# 05_COMMUNICATION.net
KiCad netlist of a schematic drawn in Altium Designer
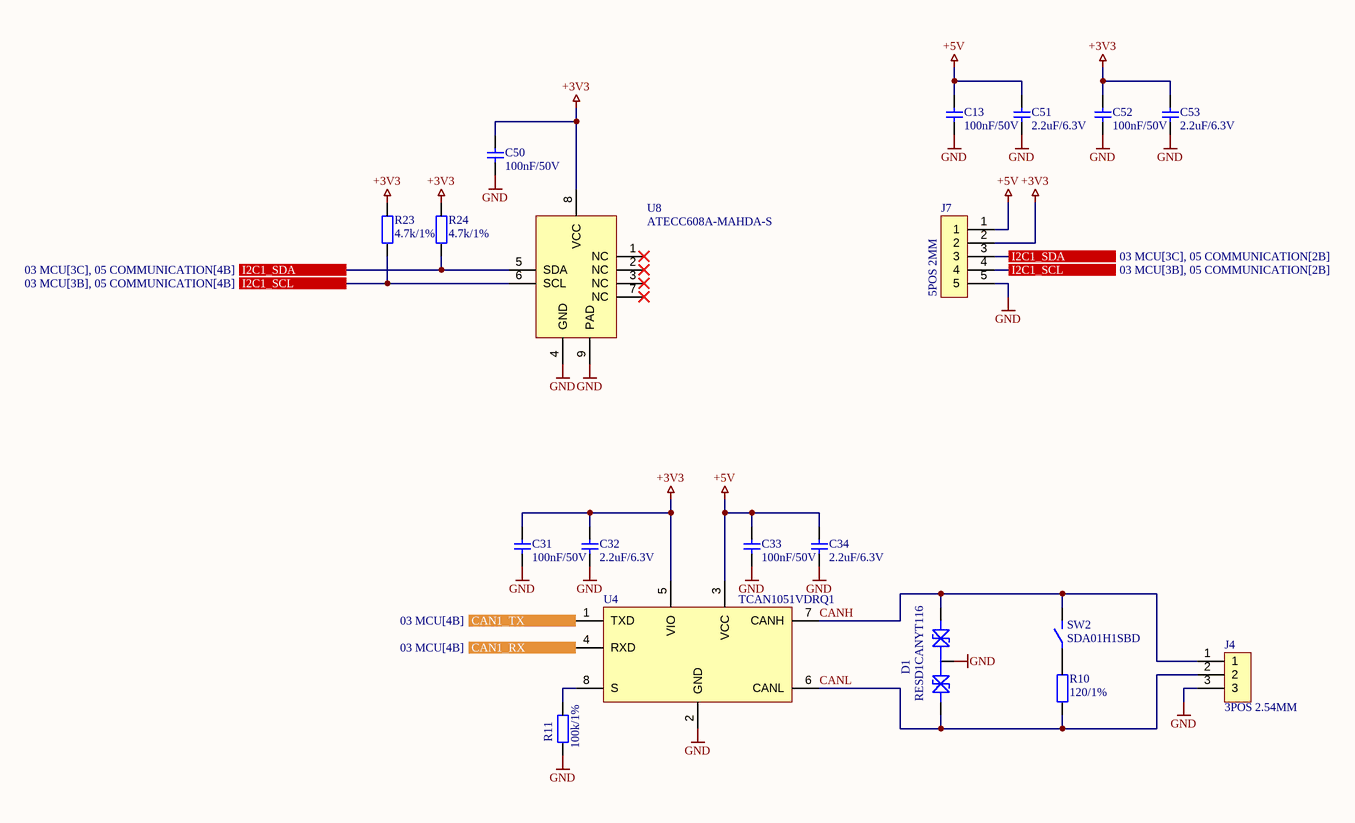
[diagram p0: 05 COMMUNICATION.SchDoc]

(export (version "E")
  (design (tool "Eeschema 10.0.6"))
  (components
    (comp (ref "C13")
      (value "100nF/50V")
      (footprint "CAPC1005X06M-0402")
      (description "0.1 µF ±10% 50V Ceramic Capacitor X7R 0402 (1005 Metric)")
      (fields (field (name "MPN") "GRM155R71H104KE14D"))
      (libsource (lib "Symbol") (part "GRM155R71H104KE14D"))
    )
    (comp (ref "C31")
      (value "100nF/50V")
      (footprint "CAPC1005X06M-0402")
      (description "0.1 µF ±10% 50V Ceramic Capacitor X7R 0402 (1005 Metric)")
      (fields (field (name "MPN") "GRM155R71H104KE14D"))
      (libsource (lib "Symbol") (part "GRM155R71H104KE14D"))
    )
    (comp (ref "C32")
      (value "2.2uF/6.3V")
      (footprint "CAPC1005X06M-0402")
      (description "2.2 µF ±10% 6.3V Ceramic Capacitor X6S 0402 (1005 Metric)")
      (fields (field (name "MPN") "GRM155C80J225KE95D"))
      (libsource (lib "Symbol") (part "GRM155C80J225KE95D"))
    )
    (comp (ref "C33")
      (value "100nF/50V")
      (footprint "CAPC1005X06M-0402")
      (description "0.1 µF ±10% 50V Ceramic Capacitor X7R 0402 (1005 Metric)")
      (fields (field (name "MPN") "GRM155R71H104KE14D"))
      (libsource (lib "Symbol") (part "GRM155R71H104KE14D"))
    )
    (comp (ref "C34")
      (value "2.2uF/6.3V")
      (footprint "CAPC1005X06M-0402")
      (description "2.2 µF ±10% 6.3V Ceramic Capacitor X6S 0402 (1005 Metric)")
      (fields (field (name "MPN") "GRM155C80J225KE95D"))
      (libsource (lib "Symbol") (part "GRM155C80J225KE95D"))
    )
    (comp (ref "C50")
      (value "100nF/50V")
      (footprint "CAPC1005X06M-0402")
      (description "0.1 µF ±10% 50V Ceramic Capacitor X7R 0402 (1005 Metric)")
      (fields (field (name "MPN") "GRM155R71H104KE14D"))
      (libsource (lib "Symbol") (part "GRM155R71H104KE14D"))
    )
    (comp (ref "C51")
      (value "2.2uF/6.3V")
      (footprint "CAPC1005X06M-0402")
      (description "2.2 µF ±10% 6.3V Ceramic Capacitor X6S 0402 (1005 Metric)")
      (fields (field (name "MPN") "GRM155C80J225KE95D"))
      (libsource (lib "Symbol") (part "GRM155C80J225KE95D"))
    )
    (comp (ref "C52")
      (value "100nF/50V")
      (footprint "CAPC1005X06M-0402")
      (description "0.1 µF ±10% 50V Ceramic Capacitor X7R 0402 (1005 Metric)")
      (fields (field (name "MPN") "GRM155R71H104KE14D"))
      (libsource (lib "Symbol") (part "GRM155R71H104KE14D"))
    )
    (comp (ref "C53")
      (value "2.2uF/6.3V")
      (footprint "CAPC1005X06M-0402")
      (description "2.2 µF ±10% 6.3V Ceramic Capacitor X6S 0402 (1005 Metric)")
      (fields (field (name "MPN") "GRM155C80J225KE95D"))
      (libsource (lib "Symbol") (part "GRM155C80J225KE95D"))
    )
    (comp (ref "D1")
      (value "RESD1CANYT116")
      (footprint "SOT100P240X115-3N")
      (description "44V Clamp 8A (8/20µs) Ipp Tvs Diode Surface Mount SOT-23")
      (libsource (lib "Symbol") (part "RESD1CANYT116"))
    )
    (comp (ref "J4")
      (value "3POS 2.54MM")
      (footprint "282834-3")
      (description "3 Position Wire to Board Terminal Block Horizontal with Board 0.100\" (2.54mm) Through Hole")
      (fields (field (name "MPN") "282834-3"))
      (libsource (lib "Symbol") (part "282834-3"))
    )
    (comp (ref "J7")
      (value "5POS 2MM")
      (footprint "B5B-PH-K-S")
      (description "Connector Header Through Hole 5 position 0.079\" (2.00mm)")
      (fields (field (name "MPN") "B5B-PH-K-S"))
      (libsource (lib "Symbol") (part "B5B-PH-K-S"))
    )
    (comp (ref "R10")
      (value "120/1%")
      (footprint "RESC1005X04M-0402")
      (description "120 Ohms ±1% 0.063W, 1/16W Chip Resistor 0402 (1005 Metric) Moisture Resistant Thick Film")
      (fields (field (name "MPN") "RC0402FR-07120RL"))
      (libsource (lib "Symbol") (part "RC0402FR-07120RL"))
    )
    (comp (ref "R11")
      (value "100k/1%")
      (footprint "RESC1005X04M-0402")
      (description "100 kOhms ±1% 0.063W, 1/16W Chip Resistor 0402 (1005 Metric) Moisture Resistant Thick Film")
      (fields (field (name "MPN") "RC0402FR-07100KL"))
      (libsource (lib "Symbol") (part "RC0402FR-07100KL"))
    )
    (comp (ref "R23")
      (value "4.7k/1%")
      (footprint "RESC1005X04M-0402")
      (description "4.7 kOhms ±1% 0.063W, 1/16W Chip Resistor 0402 (1005 Metric) Moisture Resistant Thick Film")
      (fields (field (name "MPN") "RC0402FR-074K7L"))
      (libsource (lib "Symbol") (part "RC0402FR-074K7L"))
    )
    (comp (ref "R24")
      (value "4.7k/1%")
      (footprint "RESC1005X04M-0402")
      (description "4.7 kOhms ±1% 0.063W, 1/16W Chip Resistor 0402 (1005 Metric) Moisture Resistant Thick Film")
      (fields (field (name "MPN") "RC0402FR-074K7L"))
      (libsource (lib "Symbol") (part "RC0402FR-074K7L"))
    )
    (comp (ref "SW2")
      (value "SDA01H1SBD")
      (footprint "SDA01H1SB")
      (description "Dip Switch SPST 1 Position Surface Mount Slide (Standard) Actuator 25mA 24VDC")
      (libsource (lib "Symbol") (part "SDA01H1SBD"))
    )
    (comp (ref "U4")
      (value "TCAN1051VDRQ1")
      (footprint "SOIC127P600X175-8N")
      (description "1/1 Transceiver Half CANbus 8-SOIC")
      (libsource (lib "Symbol") (part "TCAN1051VDRQ1"))
    )
    (comp (ref "U8")
      (value "ATECC608A-MAHDA-S")
      (footprint "SON50P200X60_HS-9N")
      (description "Authentication Chip 8-UDFN (2x3)")
      (libsource (lib "Symbol") (part "ATECC608A-MAHDA-S"))
    )
  )
  (nets
    (net (code "1") (name "+3V3") (class "Default")
      (node (ref "C31") (pin "2") (pinfunction "2_2") (pintype "passive"))
      (node (ref "C32") (pin "2") (pinfunction "2_2") (pintype "passive"))
      (node (ref "C50") (pin "2") (pinfunction "2_2") (pintype "passive"))
      (node (ref "C52") (pin "2") (pinfunction "2_2") (pintype "passive"))
      (node (ref "C53") (pin "2") (pinfunction "2_2") (pintype "passive"))
      (node (ref "J7") (pin "2") (pinfunction "2_2") (pintype "passive"))
      (node (ref "R23") (pin "2") (pinfunction "2_2") (pintype "passive"))
      (node (ref "R24") (pin "2") (pinfunction "2_2") (pintype "passive"))
      (node (ref "U4") (pin "5") (pinfunction "VIO_5") (pintype "passive"))
      (node (ref "U8") (pin "8") (pinfunction "VCC_8") (pintype "passive"))
    )
    (net (code "2") (name "+5V") (class "Default")
      (node (ref "C13") (pin "2") (pinfunction "2_2") (pintype "passive"))
      (node (ref "C33") (pin "2") (pinfunction "2_2") (pintype "passive"))
      (node (ref "C34") (pin "2") (pinfunction "2_2") (pintype "passive"))
      (node (ref "C51") (pin "2") (pinfunction "2_2") (pintype "passive"))
      (node (ref "J7") (pin "1") (pinfunction "1_1") (pintype "passive"))
      (node (ref "U4") (pin "3") (pinfunction "VCC_3") (pintype "passive"))
    )
    (net (code "3") (name "/CAN1_RX") (class "Default")
      (node (ref "U4") (pin "4") (pinfunction "RXD_4") (pintype "passive"))
    )
    (net (code "4") (name "/CAN1_TX") (class "Default")
      (node (ref "U4") (pin "1") (pinfunction "TXD_1") (pintype "passive"))
    )
    (net (code "5") (name "/CANH") (class "Default")
      (node (ref "D1") (pin "1") (pinfunction "1_1") (pintype "passive"))
      (node (ref "J4") (pin "1") (pinfunction "1_1") (pintype "passive"))
      (node (ref "SW2") (pin "2") (pinfunction "2_2") (pintype "passive"))
      (node (ref "U4") (pin "7") (pinfunction "CANH_7") (pintype "passive"))
    )
    (net (code "6") (name "/CANL") (class "Default")
      (node (ref "D1") (pin "2") (pinfunction "2_2") (pintype "passive"))
      (node (ref "J4") (pin "2") (pinfunction "2_2") (pintype "passive"))
      (node (ref "R10") (pin "1") (pinfunction "1_1") (pintype "passive"))
      (node (ref "U4") (pin "6") (pinfunction "CANL_6") (pintype "passive"))
    )
    (net (code "7") (name "/I2C1_SCL") (class "Default")
      (node (ref "J7") (pin "4") (pinfunction "4_4") (pintype "passive"))
      (node (ref "R23") (pin "1") (pinfunction "1_1") (pintype "passive"))
      (node (ref "U8") (pin "6") (pinfunction "SCL_6") (pintype "passive"))
    )
    (net (code "8") (name "/I2C1_SDA") (class "Default")
      (node (ref "J7") (pin "3") (pinfunction "3_3") (pintype "passive"))
      (node (ref "R24") (pin "1") (pinfunction "1_1") (pintype "passive"))
      (node (ref "U8") (pin "5") (pinfunction "SDA_5") (pintype "passive"))
    )
    (net (code "9") (name "GND") (class "Default")
      (node (ref "C13") (pin "1") (pinfunction "1_1") (pintype "passive"))
      (node (ref "C31") (pin "1") (pinfunction "1_1") (pintype "passive"))
      (node (ref "C32") (pin "1") (pinfunction "1_1") (pintype "passive"))
      (node (ref "C33") (pin "1") (pinfunction "1_1") (pintype "passive"))
      (node (ref "C34") (pin "1") (pinfunction "1_1") (pintype "passive"))
      (node (ref "C50") (pin "1") (pinfunction "1_1") (pintype "passive"))
      (node (ref "C51") (pin "1") (pinfunction "1_1") (pintype "passive"))
      (node (ref "C52") (pin "1") (pinfunction "1_1") (pintype "passive"))
      (node (ref "C53") (pin "1") (pinfunction "1_1") (pintype "passive"))
      (node (ref "D1") (pin "3") (pinfunction "3_3") (pintype "passive"))
      (node (ref "J4") (pin "3") (pinfunction "3_3") (pintype "passive"))
      (node (ref "J7") (pin "5") (pinfunction "5_5") (pintype "passive"))
      (node (ref "R11") (pin "1") (pinfunction "1_1") (pintype "passive"))
      (node (ref "U4") (pin "2") (pinfunction "GND_2") (pintype "passive"))
      (node (ref "U8") (pin "4") (pinfunction "GND_4") (pintype "passive"))
      (node (ref "U8") (pin "9") (pinfunction "PAD_9") (pintype "passive"))
    )
    (net (code "10") (name "Net-(R10-Pad2)") (class "Default")
      (node (ref "R10") (pin "2") (pinfunction "2_2") (pintype "passive"))
      (node (ref "SW2") (pin "1") (pinfunction "1_1") (pintype "passive"))
    )
    (net (code "11") (name "Net-(U4-S)") (class "Default")
      (node (ref "R11") (pin "2") (pinfunction "2_2") (pintype "passive"))
      (node (ref "U4") (pin "8") (pinfunction "S_8") (pintype "passive"))
    )
    (net (code "12") (name "unconnected-(U8-NC-Pad1)") (class "Default")
      (node (ref "U8") (pin "1") (pinfunction "NC_1") (pintype "passive+no_connect"))
    )
    (net (code "13") (name "unconnected-(U8-NC-Pad2)") (class "Default")
      (node (ref "U8") (pin "2") (pinfunction "NC_2") (pintype "passive+no_connect"))
    )
    (net (code "14") (name "unconnected-(U8-NC-Pad3)") (class "Default")
      (node (ref "U8") (pin "3") (pinfunction "NC_3") (pintype "passive+no_connect"))
    )
    (net (code "15") (name "unconnected-(U8-NC-Pad7)") (class "Default")
      (node (ref "U8") (pin "7") (pinfunction "NC_7") (pintype "passive+no_connect"))
    )
  )
)
